# PowerManagement.net
KiCad netlist of a schematic drawn in Altium Designer
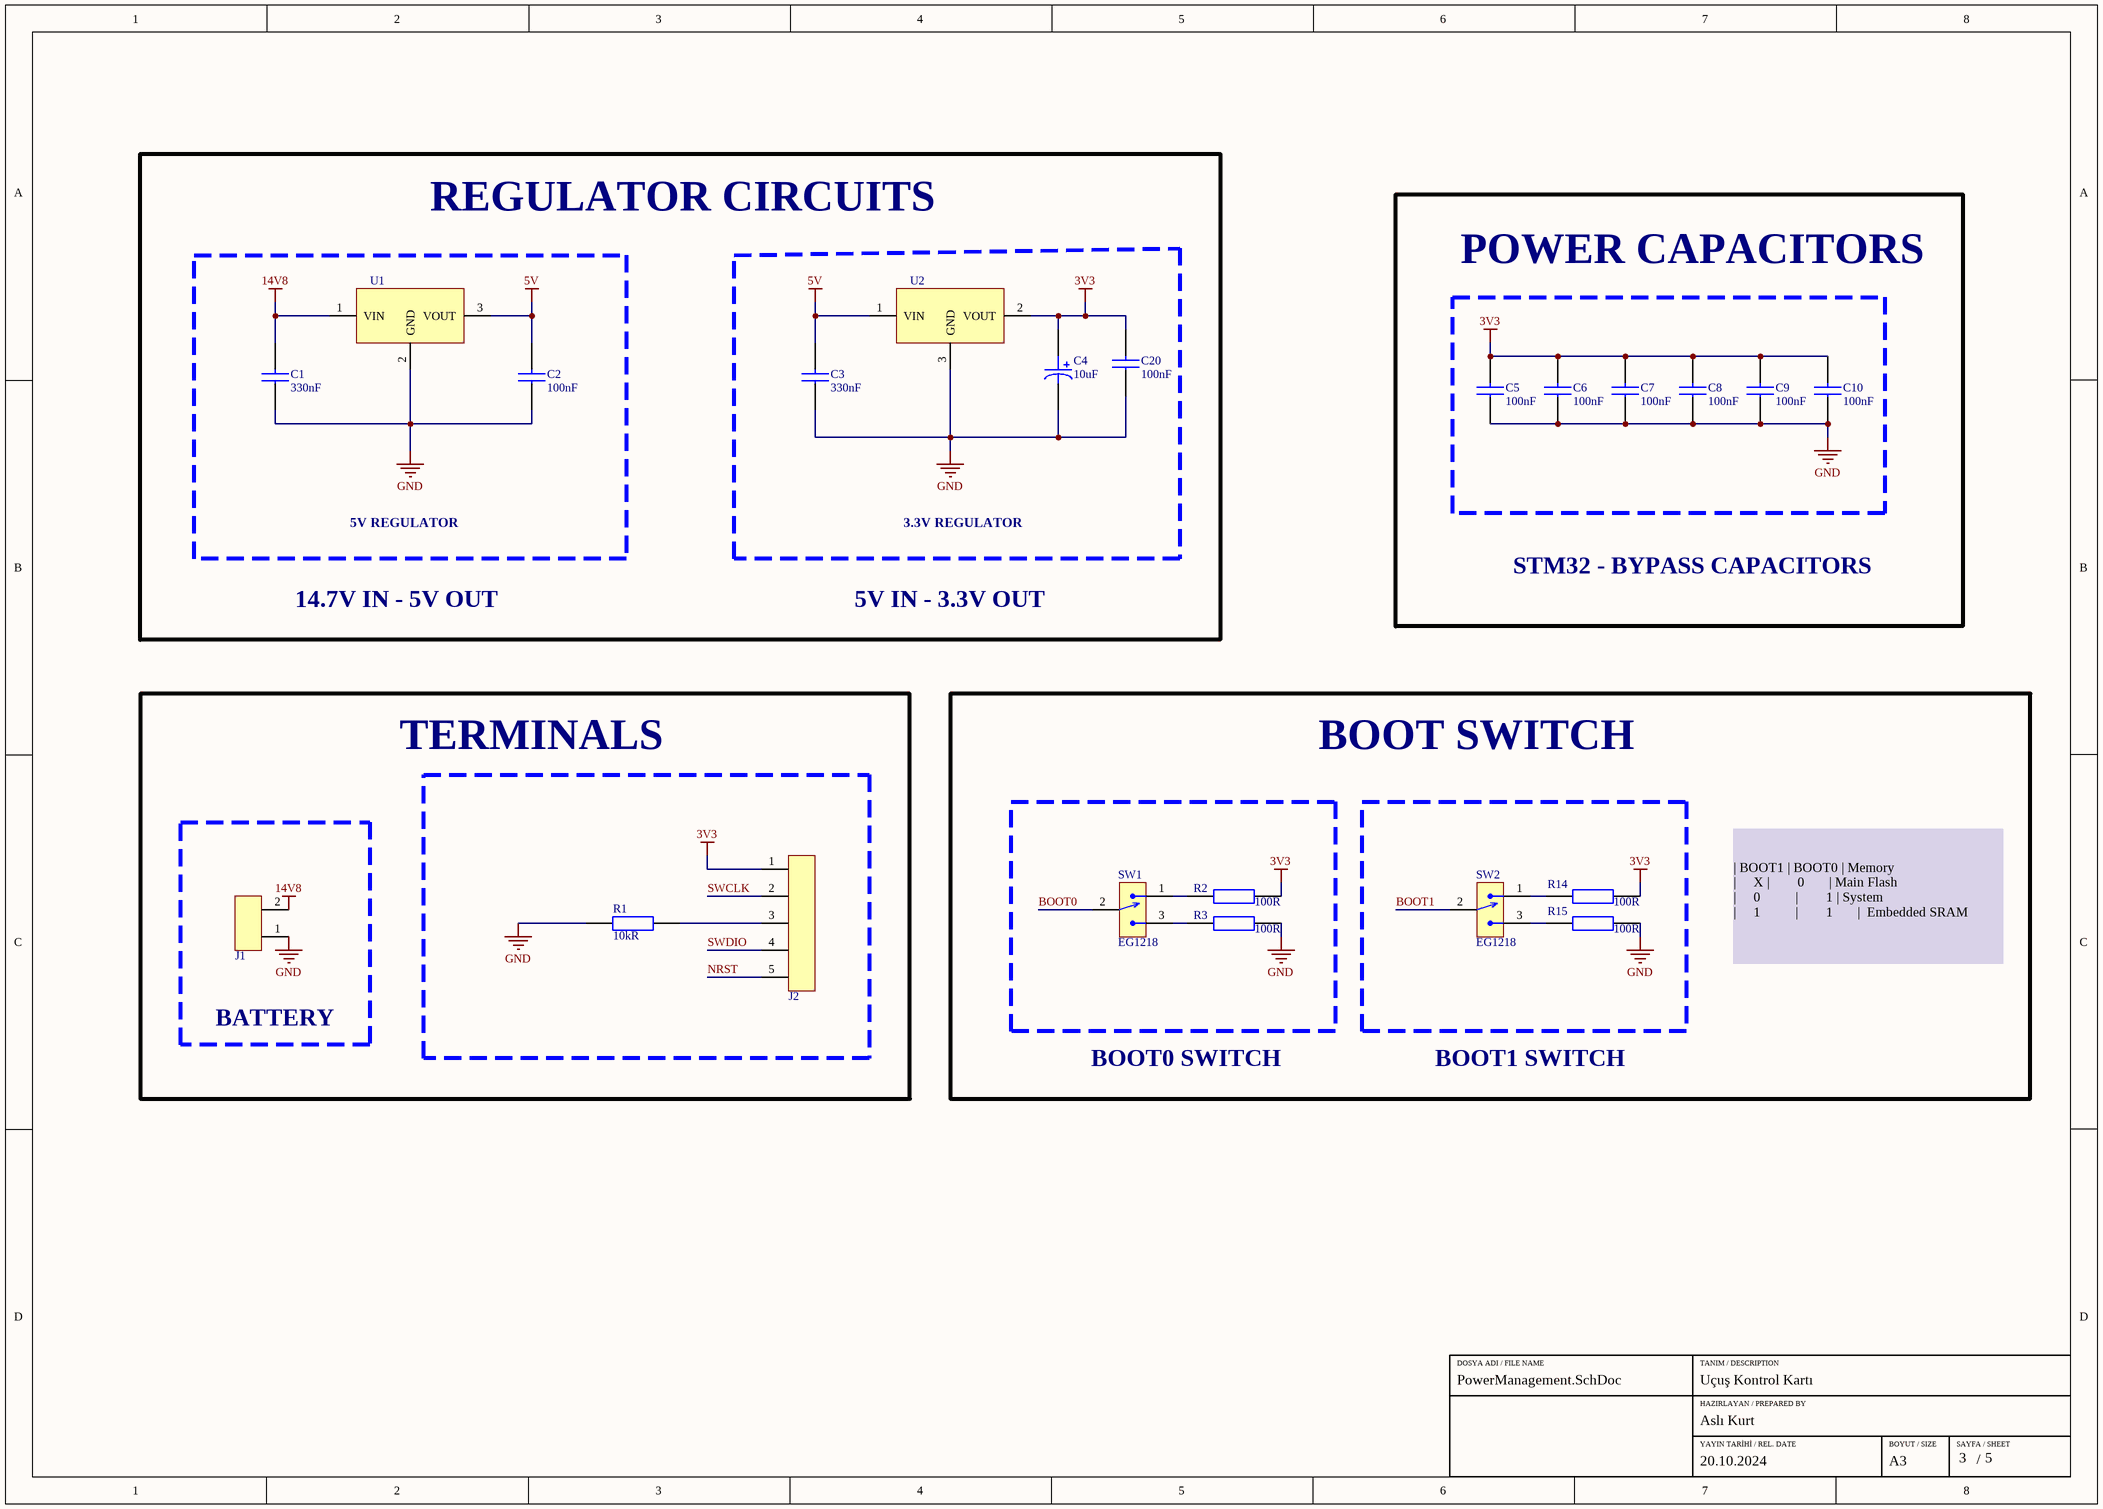
[diagram p0: PowerManagement.SchDoc]

(export (version "E")
  (design (tool "Eeschema 10.0.6"))
  (components
    (comp (ref "C1")
      (value "CGA3E3X7R1H334K080AB")
      (footprint "CAP_0603")
      (description "Multilayer Ceramic Capacitor, 0.33 uF, 50 V, ± 10%, X7R, 0603 [1608 Metric]")
      (fields
        (field (name "MANUFACTURER") "TDK")
        (field (name "TOLERANCE") "10%")
        (field (name "CAPACITANCE") "330nF")
        (field (name "DESIGNEDBY") "Aslı Kurt")
      )
      (libsource (lib "MyLibrary") (part "CAP CER 330nF 0603"))
    )
    (comp (ref "C2")
      (value "C0603C104K5RACTU")
      (footprint "CAP_0603")
      (description "CAP CER 100nF %10 0603 SMD")
      (fields
        (field (name "MANUFACTURER") "KEMET")
        (field (name "TOLERANCE") "10%")
        (field (name "CAPACITANCE") "100nF")
        (field (name "DESIGNEDBY") "Aslı Kurt")
      )
      (libsource (lib "MyLibrary") (part "CAP CER 100nF 0603"))
    )
    (comp (ref "C3")
      (value "CGA3E3X7R1H334K080AB")
      (footprint "CAP_0603")
      (description "Multilayer Ceramic Capacitor, 0.33 uF, 50 V, ± 10%, X7R, 0603 [1608 Metric]")
      (fields
        (field (name "MANUFACTURER") "TDK")
        (field (name "TOLERANCE") "10%")
        (field (name "CAPACITANCE") "330nF")
        (field (name "DESIGNEDBY") "Aslı Kurt")
      )
      (libsource (lib "MyLibrary") (part "CAP CER 330nF 0603"))
    )
    (comp (ref "C4")
      (value "865080642006")
      (footprint "CAP_RADIAL_D5_P5.5_SMD")
      (description "CAP ALUM 10UF 20% 50V SMD")
      (fields
        (field (name "MANUFACTURER") "Wurth Electronics")
        (field (name "TOLERANCE") "20%")
        (field (name "CAPACITANCE") "10uF")
        (field (name "DESIGNEDBY") "Aslı Kurt")
      )
      (libsource (lib "MyLibrary") (part "CAP ALU ELEC 10uF  50V"))
    )
    (comp (ref "C5")
      (value "C0603C104K5RACTU")
      (footprint "CAP_0603")
      (description "CAP CER 100nF %10 0603 SMD")
      (fields
        (field (name "MANUFACTURER") "KEMET")
        (field (name "TOLERANCE") "10%")
        (field (name "CAPACITANCE") "100nF")
        (field (name "DESIGNEDBY") "Aslı Kurt")
      )
      (libsource (lib "MyLibrary") (part "CAP CER 100nF 0603"))
    )
    (comp (ref "C6")
      (value "C0603C104K5RACTU")
      (footprint "CAP_0603")
      (description "CAP CER 100nF %10 0603 SMD")
      (fields
        (field (name "MANUFACTURER") "KEMET")
        (field (name "TOLERANCE") "10%")
        (field (name "CAPACITANCE") "100nF")
        (field (name "DESIGNEDBY") "Aslı Kurt")
      )
      (libsource (lib "MyLibrary") (part "CAP CER 100nF 0603"))
    )
    (comp (ref "C7")
      (value "C0603C104K5RACTU")
      (footprint "CAP_0603")
      (description "CAP CER 100nF %10 0603 SMD")
      (fields
        (field (name "MANUFACTURER") "KEMET")
        (field (name "TOLERANCE") "10%")
        (field (name "CAPACITANCE") "100nF")
        (field (name "DESIGNEDBY") "Aslı Kurt")
      )
      (libsource (lib "MyLibrary") (part "CAP CER 100nF 0603"))
    )
    (comp (ref "C8")
      (value "C0603C104K5RACTU")
      (footprint "CAP_0603")
      (description "CAP CER 100nF %10 0603 SMD")
      (fields
        (field (name "MANUFACTURER") "KEMET")
        (field (name "TOLERANCE") "10%")
        (field (name "CAPACITANCE") "100nF")
        (field (name "DESIGNEDBY") "Aslı Kurt")
      )
      (libsource (lib "MyLibrary") (part "CAP CER 100nF 0603"))
    )
    (comp (ref "C9")
      (value "C0603C104K5RACTU")
      (footprint "CAP_0603")
      (description "CAP CER 100nF %10 0603 SMD")
      (fields
        (field (name "MANUFACTURER") "KEMET")
        (field (name "TOLERANCE") "10%")
        (field (name "CAPACITANCE") "100nF")
        (field (name "DESIGNEDBY") "Aslı Kurt")
      )
      (libsource (lib "MyLibrary") (part "CAP CER 100nF 0603"))
    )
    (comp (ref "C10")
      (value "C0603C104K5RACTU")
      (footprint "CAP_0603")
      (description "CAP CER 100nF %10 0603 SMD")
      (fields
        (field (name "MANUFACTURER") "KEMET")
        (field (name "TOLERANCE") "10%")
        (field (name "CAPACITANCE") "100nF")
        (field (name "DESIGNEDBY") "Aslı Kurt")
      )
      (libsource (lib "MyLibrary") (part "CAP CER 100nF 0603"))
    )
    (comp (ref "C20")
      (value "C0603C104K5RACTU")
      (footprint "CAP_0603")
      (description "CAP CER 100nF %10 0603 SMD")
      (fields
        (field (name "MANUFACTURER") "KEMET")
        (field (name "TOLERANCE") "10%")
        (field (name "CAPACITANCE") "100nF")
        (field (name "DESIGNEDBY") "Aslı Kurt")
      )
      (libsource (lib "MyLibrary") (part "CAP CER 100nF 0603"))
    )
    (comp (ref "J1")
      (value "282836-2")
      (footprint "TERMINAL")
      (description "Connector, Terminal Block; Wire Receptacle; 2 Pos.; 16-30 AWG; 0.197 in. CL; Sid")
      (fields
        (field (name "MANUFACTURER") "TE Connectivity")
        (field (name "VOLTAGE") "300V")
        (field (name "DESIGNEDBY") "Aslı Kurt")
      )
      (libsource (lib "MyLibrary") (part "2x1 TERMINAL 5mm"))
    )
    (comp (ref "J2")
      (value "61300511121")
      (footprint "5x1 Male Header 2.54mm")
      (fields (field (name "DESIGNEDBY") "Aslı Kurt"))
      (libsource (lib "MyLibrary") (part "5x1 Male Header 2.54mm"))
    )
    (comp (ref "R1")
      (value "RC0805JR-0710KL")
      (footprint "RES_0805")
      (description "RES 10K OHM 5% 1/8W 0805")
      (fields
        (field (name "MANUFACTURER") "Yageo")
        (field (name "TOLERANCE") "5%")
        (field (name "RESISTANCE") "10kR")
        (field (name "DESIGNEDBY") "Aslı Kurt")
      )
      (libsource (lib "MyLibrary") (part "RES 10K OHM 0805"))
    )
    (comp (ref "R2")
      (value "RC0603JR-07100RL")
      (footprint "RES_0603")
      (description "RES 100 %5 OHM 0603 SMD")
      (fields
        (field (name "MANUFACTURER") "Yageo")
        (field (name "TOLERANCE") "5%")
        (field (name "RESISTANCE") "100R")
        (field (name "DESIGNEDBY") "Aslı Kurt")
      )
      (libsource (lib "MyLibrary") (part "RES 100 OHM 0603"))
    )
    (comp (ref "R3")
      (value "RC0603JR-07100RL")
      (footprint "RES_0603")
      (description "RES 100 %5 OHM 0603 SMD")
      (fields
        (field (name "MANUFACTURER") "Yageo")
        (field (name "TOLERANCE") "5%")
        (field (name "RESISTANCE") "100R")
        (field (name "DESIGNEDBY") "Aslı Kurt")
      )
      (libsource (lib "MyLibrary") (part "RES 100 OHM 0603"))
    )
    (comp (ref "R14")
      (value "RC0603JR-07100RL")
      (footprint "RES_0603")
      (description "RES 100 %5 OHM 0603 SMD")
      (fields
        (field (name "MANUFACTURER") "Yageo")
        (field (name "TOLERANCE") "5%")
        (field (name "RESISTANCE") "100R")
        (field (name "DESIGNEDBY") "Aslı Kurt")
      )
      (libsource (lib "MyLibrary") (part "RES 100 OHM 0603"))
    )
    (comp (ref "R15")
      (value "RC0603JR-07100RL")
      (footprint "RES_0603")
      (description "RES 100 %5 OHM 0603 SMD")
      (fields
        (field (name "MANUFACTURER") "Yageo")
        (field (name "TOLERANCE") "5%")
        (field (name "RESISTANCE") "100R")
        (field (name "DESIGNEDBY") "Aslı Kurt")
      )
      (libsource (lib "MyLibrary") (part "RES 100 OHM 0603"))
    )
    (comp (ref "SW1")
      (value "EG1218")
      (footprint "SWITCHSLIDE_1POS_DIP")
      (description "Slide Switch, SPDT, ON-ON, 200 mA, 30V DC, TH, PC Pin, EG Series ¦ E-Switch EG1218")
      (fields (field (name "MANUFACTURER") "E-Switch") (field (name "DESIGNEDBY") "Aslı Kurt"))
      (libsource (lib "MyLibrary") (part "EG1218"))
    )
    (comp (ref "SW2")
      (value "EG1218")
      (footprint "SWITCHSLIDE_1POS_DIP")
      (description "Slide Switch, SPDT, ON-ON, 200 mA, 30V DC, TH, PC Pin, EG Series ¦ E-Switch EG1218")
      (fields (field (name "MANUFACTURER") "E-Switch") (field (name "DESIGNEDBY") "Aslı Kurt"))
      (libsource (lib "MyLibrary") (part "EG1218"))
    )
    (comp (ref "U1")
      (value "L7805CD2T-TR")
      (footprint "D2PAK-TO-263-3")
      (description "Standard Regulator Pos 5V 1.5A 3-Pin(2+Tab) D2PAK T/R / IC REG LDO 5V 1.5A D2PAK")
      (fields (field (name "MANUFACTURER") "STMicroelectronics") (field (name "DESIGNEDBY") "Aslı Kurt"))
      (libsource (lib "MyLibrary") (part "L7805CD2T-TR"))
    )
    (comp (ref "U2")
      (value "LD29150DT33R")
      (footprint "DPAK-TO252")
      (description "LD29150 Series 3.3 V 1.5 A Fixed Output SMT LDO Voltage Regulator - TO-252")
      (fields (field (name "MANUFACTURER") "STMicroelectronics") (field (name "DESIGNEDBY") "Aslı Kurt"))
      (libsource (lib "MyLibrary") (part "LD29150DT33R"))
    )
  )
  (nets
    (net (code "1") (name "/BOOT0") (class "Default")
      (node (ref "SW1") (pin "2") (pinfunction "2_2") (pintype "passive"))
    )
    (net (code "2") (name "/BOOT1") (class "Default")
      (node (ref "SW2") (pin "2") (pinfunction "2_2") (pintype "passive"))
    )
    (net (code "3") (name "/NRST") (class "Default")
      (node (ref "J2") (pin "5") (pinfunction "5_5") (pintype "passive"))
    )
    (net (code "4") (name "/SWCLK") (class "Default")
      (node (ref "J2") (pin "2") (pinfunction "2_2") (pintype "power_in"))
    )
    (net (code "5") (name "/SWDIO") (class "Default")
      (node (ref "J2") (pin "4") (pinfunction "4_4") (pintype "power_in"))
    )
    (net (code "6") (name "3V3") (class "Default")
      (node (ref "C10") (pin "2") (pinfunction "2_2") (pintype "passive"))
      (node (ref "C20") (pin "2") (pinfunction "2_2") (pintype "passive"))
      (node (ref "C4") (pin "1") (pinfunction "1_1") (pintype "passive"))
      (node (ref "C5") (pin "2") (pinfunction "2_2") (pintype "passive"))
      (node (ref "C6") (pin "2") (pinfunction "2_2") (pintype "passive"))
      (node (ref "C7") (pin "2") (pinfunction "2_2") (pintype "passive"))
      (node (ref "C8") (pin "2") (pinfunction "2_2") (pintype "passive"))
      (node (ref "C9") (pin "2") (pinfunction "2_2") (pintype "passive"))
      (node (ref "J2") (pin "1") (pinfunction "1_1") (pintype "power_in"))
      (node (ref "R14") (pin "2") (pinfunction "2_2") (pintype "passive"))
      (node (ref "R2") (pin "2") (pinfunction "2_2") (pintype "passive"))
      (node (ref "U2") (pin "2") (pinfunction "VOUT_2") (pintype "passive"))
    )
    (net (code "7") (name "5V") (class "Default")
      (node (ref "C2") (pin "2") (pinfunction "2_2") (pintype "passive"))
      (node (ref "C3") (pin "2") (pinfunction "2_2") (pintype "passive"))
      (node (ref "U1") (pin "3") (pinfunction "VOUT_3") (pintype "passive"))
      (node (ref "U2") (pin "1") (pinfunction "VIN_1") (pintype "passive"))
    )
    (net (code "8") (name "14V8") (class "Default")
      (node (ref "C1") (pin "2") (pinfunction "2_2") (pintype "passive"))
      (node (ref "J1") (pin "2") (pinfunction "2_2") (pintype "passive"))
      (node (ref "U1") (pin "1") (pinfunction "VIN_1") (pintype "passive"))
    )
    (net (code "9") (name "GND") (class "Default")
      (node (ref "C1") (pin "1") (pinfunction "1_1") (pintype "passive"))
      (node (ref "C10") (pin "1") (pinfunction "1_1") (pintype "passive"))
      (node (ref "C2") (pin "1") (pinfunction "1_1") (pintype "passive"))
      (node (ref "C20") (pin "1") (pinfunction "1_1") (pintype "passive"))
      (node (ref "C3") (pin "1") (pinfunction "1_1") (pintype "passive"))
      (node (ref "C4") (pin "2") (pinfunction "2_2") (pintype "passive"))
      (node (ref "C5") (pin "1") (pinfunction "1_1") (pintype "passive"))
      (node (ref "C6") (pin "1") (pinfunction "1_1") (pintype "passive"))
      (node (ref "C7") (pin "1") (pinfunction "1_1") (pintype "passive"))
      (node (ref "C8") (pin "1") (pinfunction "1_1") (pintype "passive"))
      (node (ref "C9") (pin "1") (pinfunction "1_1") (pintype "passive"))
      (node (ref "J1") (pin "1") (pinfunction "1_1") (pintype "passive"))
      (node (ref "R1") (pin "1") (pinfunction "1_1") (pintype "passive"))
      (node (ref "R15") (pin "2") (pinfunction "2_2") (pintype "passive"))
      (node (ref "R3") (pin "2") (pinfunction "2_2") (pintype "passive"))
      (node (ref "U1") (pin "2") (pinfunction "GND_2") (pintype "passive"))
      (node (ref "U2") (pin "3") (pinfunction "GND_3") (pintype "passive"))
    )
    (net (code "10") (name "Net-(J2-Pad3)") (class "Default")
      (node (ref "J2") (pin "3") (pinfunction "3_3") (pintype "power_in"))
      (node (ref "R1") (pin "2") (pinfunction "2_2") (pintype "passive"))
    )
    (net (code "11") (name "Net-(R2-Pad1)") (class "Default")
      (node (ref "R2") (pin "1") (pinfunction "1_1") (pintype "passive"))
      (node (ref "SW1") (pin "1") (pinfunction "1_1") (pintype "passive"))
    )
    (net (code "12") (name "Net-(R3-Pad1)") (class "Default")
      (node (ref "R3") (pin "1") (pinfunction "1_1") (pintype "passive"))
      (node (ref "SW1") (pin "3") (pinfunction "3_3") (pintype "passive"))
    )
    (net (code "13") (name "Net-(R14-Pad1)") (class "Default")
      (node (ref "R14") (pin "1") (pinfunction "1_1") (pintype "passive"))
      (node (ref "SW2") (pin "1") (pinfunction "1_1") (pintype "passive"))
    )
    (net (code "14") (name "Net-(R15-Pad1)") (class "Default")
      (node (ref "R15") (pin "1") (pinfunction "1_1") (pintype "passive"))
      (node (ref "SW2") (pin "3") (pinfunction "3_3") (pintype "passive"))
    )
  )
)
